# MCU2.net
KiCad netlist of a schematic drawn in Altium Designer
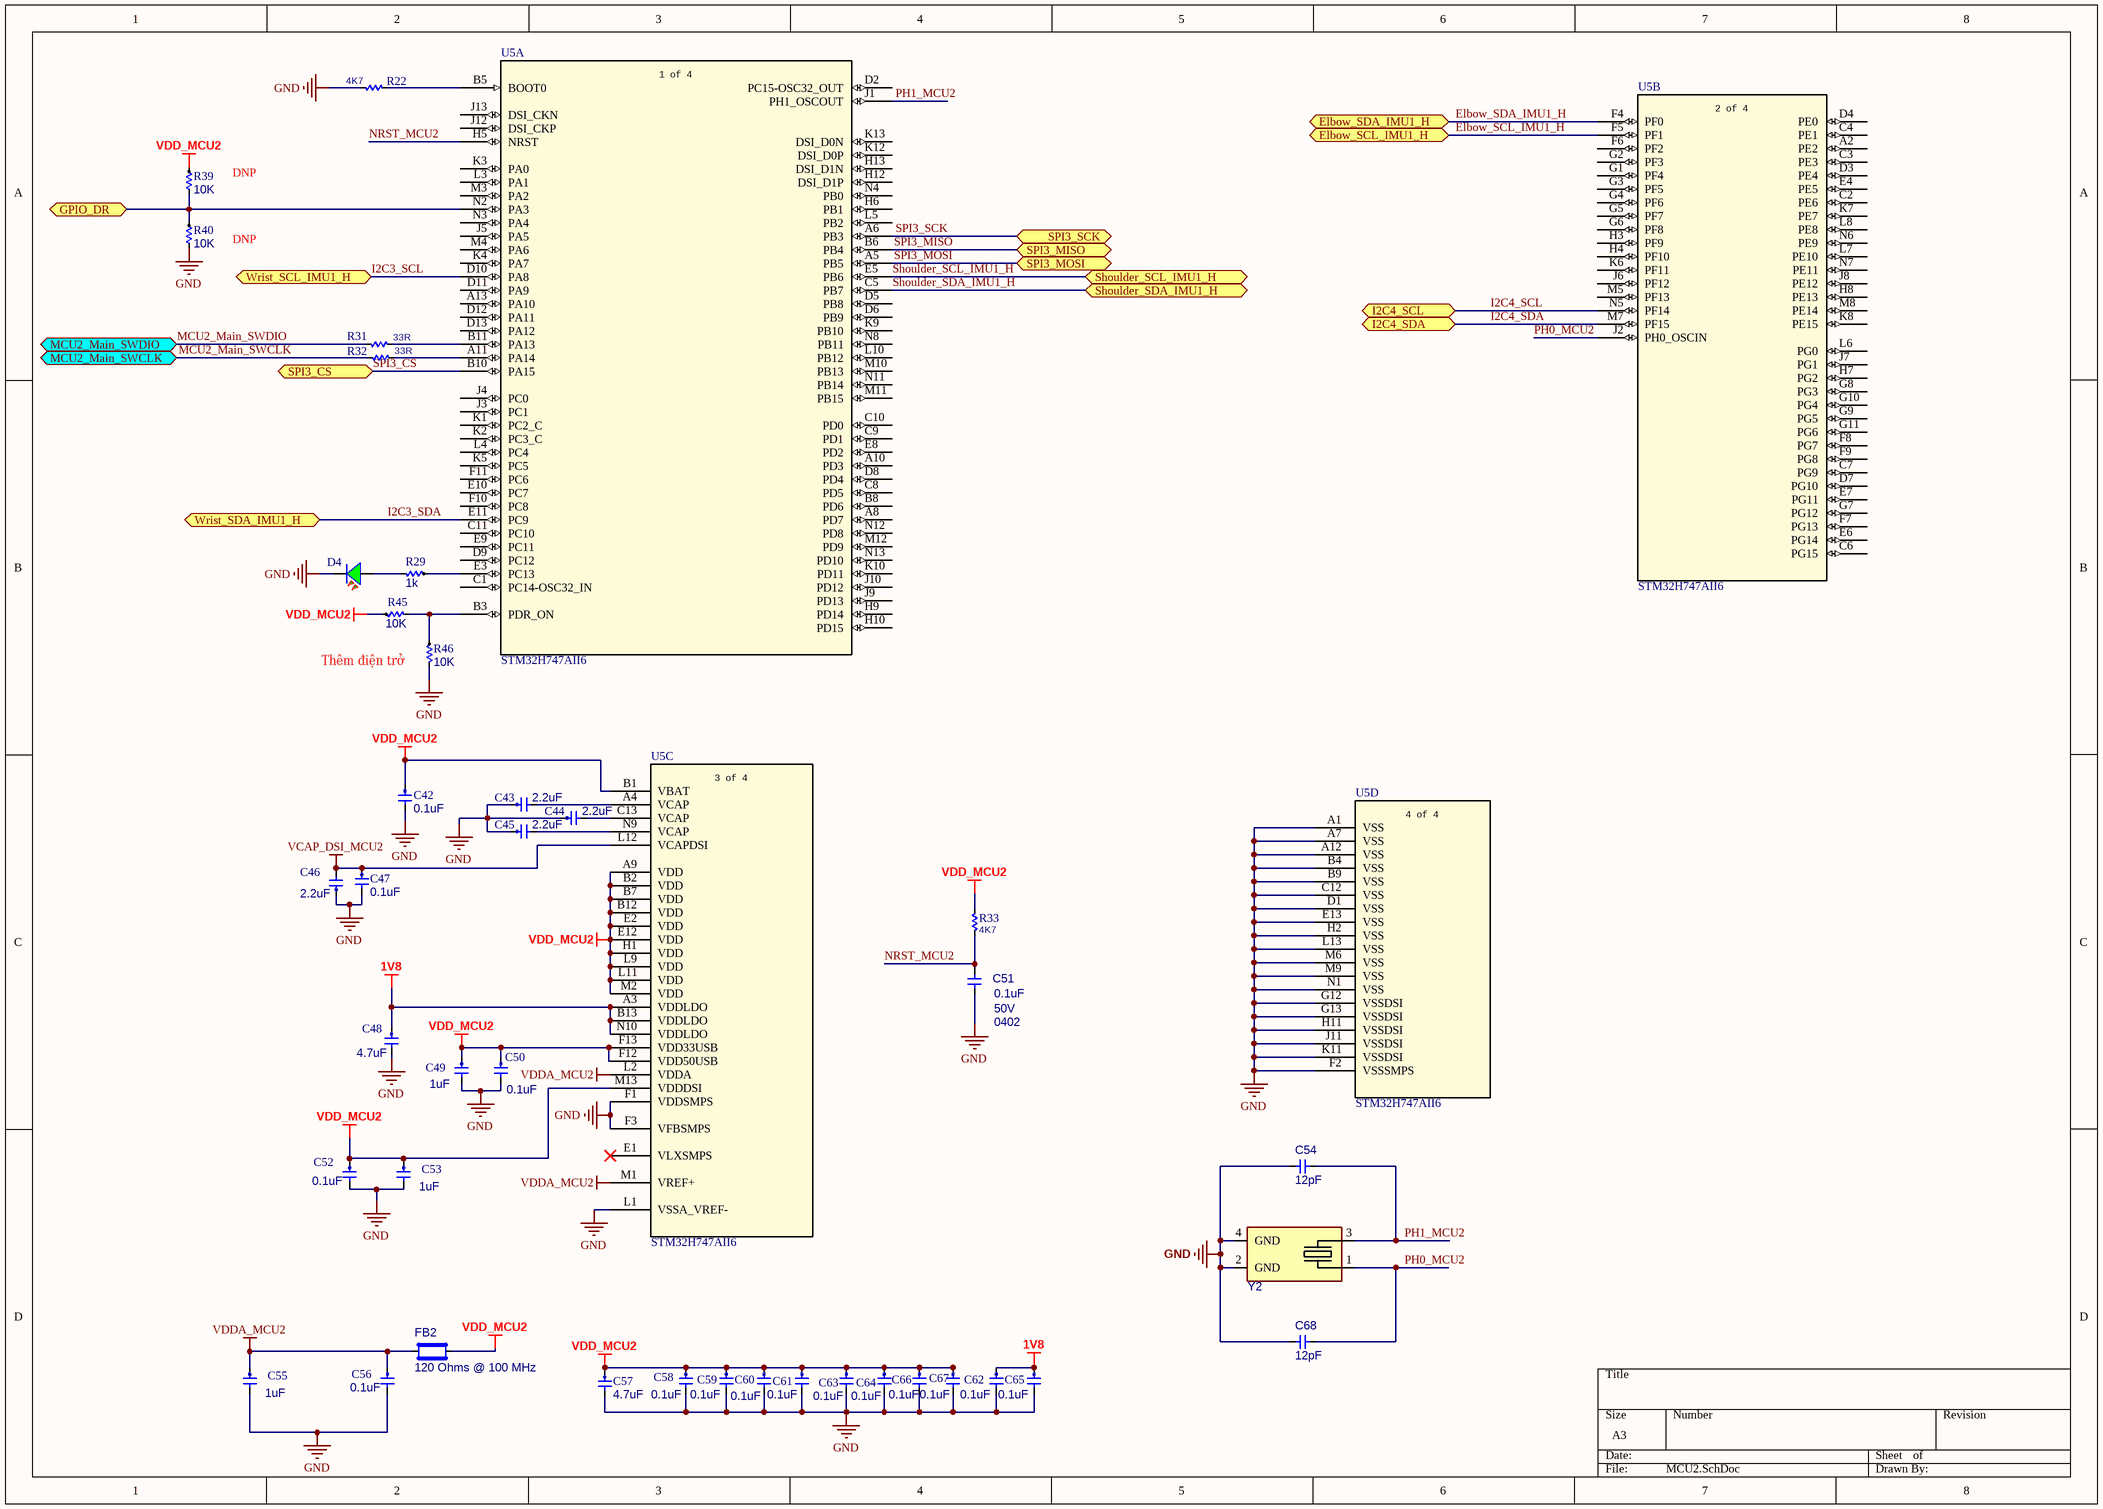
[diagram p0: MCU2.SchDoc]

(export (version "E")
  (design (tool "Eeschema 10.0.6"))
  (components
    (comp (ref "C42")
      (value "0.1uF")
      (footprint "CAP0402")
      (description "Cap 0.1uF 50V 0402")
      (fields (field (name "MP") "CC0402KRX5R9BB104") (field (name "TOLERANCE") "10%"))
      (libsource (lib "RTR (1)") (part "CAP0402 0.1uF 50V"))
    )
    (comp (ref "C43")
      (value "2.2uF")
      (footprint "CAP0402")
      (description "Cap 2.2uF 16V 0402")
      (fields (field (name "MP") "C1005X5R1C225K050BC") (field (name "VOLTAGE") "16V"))
      (libsource (lib "RTR (1)") (part "CAP0402 2.2uF 16V"))
    )
    (comp (ref "C44")
      (value "2.2uF")
      (footprint "CAP0402")
      (description "Cap 2.2uF 16V 0402")
      (fields (field (name "MP") "C1005X5R1C225K050BC") (field (name "VOLTAGE") "16V"))
      (libsource (lib "RTR (1)") (part "CAP0402 2.2uF 16V"))
    )
    (comp (ref "C45")
      (value "2.2uF")
      (footprint "CAP0402")
      (description "Cap 2.2uF 16V 0402")
      (fields (field (name "MP") "C1005X5R1C225K050BC") (field (name "VOLTAGE") "16V"))
      (libsource (lib "RTR (1)") (part "CAP0402 2.2uF 16V"))
    )
    (comp (ref "C46")
      (value "2.2uF")
      (footprint "CAP0402")
      (description "Cap 2.2uF 16V 0402")
      (fields (field (name "MP") "C1005X5R1C225K050BC") (field (name "VOLTAGE") "16V"))
      (libsource (lib "RTR (1)") (part "CAP0402 2.2uF 16V"))
    )
    (comp (ref "C47")
      (value "0.1uF")
      (footprint "CAP0402")
      (description "Cap 0.1uF 50V 0402")
      (fields (field (name "MP") "CC0402KRX5R9BB104") (field (name "TOLERANCE") "10%"))
      (libsource (lib "RTR (1)") (part "CAP0402 0.1uF 50V"))
    )
    (comp (ref "C48")
      (value "4.7uF")
      (footprint "CAP0402")
      (description "Cap 4.7uF 25V 0402")
      (fields (field (name "MP") "GRM155C61E475ME15J") (field (name "TOLERANCE") "20%"))
      (libsource (lib "RTR (1)") (part "CAP0402 4.7uF 25V"))
    )
    (comp (ref "C49")
      (value "1uF")
      (footprint "CAP0402")
      (description "Cap 1uF 50V 0402")
      (fields (field (name "MP") "GRM155R61H105KE05D") (field (name "Comment") "CAP0402 1uF 50V"))
      (libsource (lib "RTR (1)") (part "CAP0402 1uF 50V"))
    )
    (comp (ref "C50")
      (value "0.1uF")
      (footprint "CAP0402")
      (description "Cap 0.1uF 50V 0402")
      (fields (field (name "MP") "CC0402KRX5R9BB104") (field (name "TOLERANCE") "10%"))
      (libsource (lib "RTR (1)") (part "CAP0402 0.1uF 50V"))
    )
    (comp (ref "C51")
      (value "0.1uF")
      (footprint "CAP0402")
      (description "Cap 0.1uF 50V 0402")
      (fields
        (field (name "MP") "CC0402KRX5R9BB104")
        (field (name "VOLTAGE") "50V")
        (field (name "PACKAGE") "0402")
        (field (name "Comment") "CAP0402 0.1uF 50V")
      )
      (libsource (lib "RTR") (part "CAP0402 0.1uF 50V"))
    )
    (comp (ref "C52")
      (value "0.1uF")
      (footprint "CAP0402")
      (description "Cap 0.1uF 50V 0402")
      (fields (field (name "MP") "CC0402KRX5R9BB104") (field (name "TOLERANCE") "10%"))
      (libsource (lib "RTR (1)") (part "CAP0402 0.1uF 50V"))
    )
    (comp (ref "C53")
      (value "1uF")
      (footprint "CAP0402")
      (description "Cap 1uF 50V 0402")
      (fields (field (name "MP") "GRM155R61H105KE05D") (field (name "Comment") "CAP0402 1uF 50V"))
      (libsource (lib "RTR (1)") (part "CAP0402 1uF 50V"))
    )
    (comp (ref "C54")
      (value "12pF")
      (footprint "CAP0402")
      (description "Cap 12pF 50V 0402")
      (fields (field (name "Comment") "CAP0402 12pF 50V"))
      (libsource (lib "RTR") (part "CAP0402 12pF 50V"))
    )
    (comp (ref "C55")
      (value "1uF")
      (footprint "CAP0402")
      (description "Cap 1uF 50V 0402")
      (fields (field (name "MP") "GRM155R61H105KE05D") (field (name "Comment") "CAP0402 1uF 50V"))
      (libsource (lib "RTR (1)") (part "CAP0402 1uF 50V"))
    )
    (comp (ref "C56")
      (value "0.1uF")
      (footprint "CAP0402")
      (description "Cap 0.1uF 50V 0402")
      (fields (field (name "MP") "CC0402KRX5R9BB104") (field (name "TOLERANCE") "10%"))
      (libsource (lib "RTR (1)") (part "CAP0402 0.1uF 50V"))
    )
    (comp (ref "C57")
      (value "4.7uF")
      (footprint "CAP0402")
      (description "Cap 4.7uF 25V 0402")
      (fields (field (name "MP") "GRM155C61E475ME15J") (field (name "TOLERANCE") "20%"))
      (libsource (lib "RTR (1)") (part "CAP0402 4.7uF 25V"))
    )
    (comp (ref "C58")
      (value "0.1uF")
      (footprint "CAP0402")
      (description "Cap 0.1uF 50V 0402")
      (fields (field (name "MP") "CC0402KRX5R9BB104") (field (name "TOLERANCE") "10%"))
      (libsource (lib "RTR (1)") (part "CAP0402 0.1uF 50V"))
    )
    (comp (ref "C59")
      (value "0.1uF")
      (footprint "CAP0402")
      (description "Cap 0.1uF 50V 0402")
      (fields (field (name "MP") "CC0402KRX5R9BB104") (field (name "TOLERANCE") "10%"))
      (libsource (lib "RTR (1)") (part "CAP0402 0.1uF 50V"))
    )
    (comp (ref "C60")
      (value "0.1uF")
      (footprint "CAP0402")
      (description "Cap 0.1uF 50V 0402")
      (fields (field (name "MP") "CC0402KRX5R9BB104") (field (name "TOLERANCE") "10%"))
      (libsource (lib "RTR (1)") (part "CAP0402 0.1uF 50V"))
    )
    (comp (ref "C61")
      (value "0.1uF")
      (footprint "CAP0402")
      (description "Cap 0.1uF 50V 0402")
      (fields (field (name "MP") "CC0402KRX5R9BB104") (field (name "TOLERANCE") "10%"))
      (libsource (lib "RTR (1)") (part "CAP0402 0.1uF 50V"))
    )
    (comp (ref "C62")
      (value "0.1uF")
      (footprint "CAP0402")
      (description "Cap 0.1uF 50V 0402")
      (fields (field (name "MP") "CC0402KRX5R9BB104") (field (name "TOLERANCE") "10%"))
      (libsource (lib "RTR (1)") (part "CAP0402 0.1uF 50V"))
    )
    (comp (ref "C63")
      (value "0.1uF")
      (footprint "CAP0402")
      (description "Cap 0.1uF 50V 0402")
      (fields (field (name "MP") "CC0402KRX5R9BB104") (field (name "TOLERANCE") "10%"))
      (libsource (lib "RTR (1)") (part "CAP0402 0.1uF 50V"))
    )
    (comp (ref "C64")
      (value "0.1uF")
      (footprint "CAP0402")
      (description "Cap 0.1uF 50V 0402")
      (fields (field (name "MP") "CC0402KRX5R9BB104") (field (name "TOLERANCE") "10%"))
      (libsource (lib "RTR (1)") (part "CAP0402 0.1uF 50V"))
    )
    (comp (ref "C65")
      (value "0.1uF")
      (footprint "CAP0402")
      (description "Cap 0.1uF 50V 0402")
      (fields (field (name "MP") "CC0402KRX5R9BB104") (field (name "TOLERANCE") "10%"))
      (libsource (lib "RTR (1)") (part "CAP0402 0.1uF 50V"))
    )
    (comp (ref "C66")
      (value "0.1uF")
      (footprint "CAP0402")
      (description "Cap 0.1uF 50V 0402")
      (fields (field (name "MP") "CC0402KRX5R9BB104") (field (name "TOLERANCE") "10%"))
      (libsource (lib "RTR (1)") (part "CAP0402 0.1uF 50V"))
    )
    (comp (ref "C67")
      (value "0.1uF")
      (footprint "CAP0402")
      (description "Cap 0.1uF 50V 0402")
      (fields (field (name "MP") "CC0402KRX5R9BB104") (field (name "TOLERANCE") "10%"))
      (libsource (lib "RTR (1)") (part "CAP0402 0.1uF 50V"))
    )
    (comp (ref "C68")
      (value "12pF")
      (footprint "CAP0402")
      (description "Cap 12pF 50V 0402")
      (fields (field (name "Comment") "CAP0402 12pF 50V"))
      (libsource (lib "RTR") (part "CAP0402 12pF 50V"))
    )
    (comp (ref "D4")
      (value "SML-310MTT86")
      (footprint "LED0603 GREEN")
      (description "LED GREEN CLEAR 0603 SMD")
      (libsource (lib "HeraJetson_Modified") (part "CMP-01130-2"))
    )
    (comp (ref "FB2")
      (value "BLM15PX121SZ1D")
      (footprint "FERRIT0402")
      (description "120 Ohms @ 100 MHz 1 Power Line Ferrite Bead 0402 (1005 Metric) 2A 55mOhm")
      (fields (field (name "IMPEDANCE @ FREQUENCY") "120 Ohms @ 100 MHz"))
      (libsource (lib "RTR") (part "BLM15PX121SZ1D"))
    )
    (comp (ref "R22")
      (value "4K7")
      (footprint "RES0402")
      (description "RES 4K7 0402")
      (fields (field (name "MP") "RC0402JR-074K7L") (field (name "Comment") "RES0402 4K7"))
      (libsource (lib "RTR") (part "RES0402 4K7"))
    )
    (comp (ref "R29")
      (value "1k")
      (footprint "RES0402")
      (description "RES 1K 0402")
      (fields (field (name "MP") "RC0402FR-071KL") (field (name "TOLERANCE") "1%"))
      (libsource (lib "RTR (1)") (part "RES0402 1K"))
    )
    (comp (ref "R31")
      (value "33R")
      (footprint "RES0402")
      (description "RES 33R 0402")
      (fields (field (name "MP") "RC0402FR-0733RL") (field (name "Comment") "RES0402 33R"))
      (libsource (lib "RTR (1)") (part "RES0402 33R"))
    )
    (comp (ref "R32")
      (value "33R")
      (footprint "RES0402")
      (description "RES 33R 0402")
      (fields (field (name "MP") "RC0402FR-0733RL") (field (name "Comment") "RES0402 33R"))
      (libsource (lib "RTR (1)") (part "RES0402 33R"))
    )
    (comp (ref "R33")
      (value "4K7")
      (footprint "RES0402")
      (description "RES 4K7 0402")
      (fields (field (name "MP") "RC0402JR-074K7L") (field (name "Comment") "RES0402 4K7"))
      (libsource (lib "RTR") (part "RES0402 4K7"))
    )
    (comp (ref "R39")
      (value "10K")
      (footprint "RES0402")
      (description "RES 10K 0402")
      (fields (field (name "MP") "RC0402FR-0710KL") (field (name "TOLERANCE") "1%"))
      (libsource (lib "RTR (1)") (part "RES0402 10K"))
    )
    (comp (ref "R40")
      (value "10K")
      (footprint "RES0402")
      (description "RES 10K 0402")
      (fields (field (name "MP") "RC0402FR-0710KL") (field (name "TOLERANCE") "1%"))
      (libsource (lib "RTR (1)") (part "RES0402 10K"))
    )
    (comp (ref "R45")
      (value "10K")
      (footprint "RES0402")
      (description "RES 10K 0402")
      (fields (field (name "MP") "RC0402FR-0710KL") (field (name "TOLERANCE") "1%"))
      (libsource (lib "RTR (1)") (part "RES0402 10K"))
    )
    (comp (ref "R46")
      (value "10K")
      (footprint "RES0402")
      (description "RES 10K 0402")
      (fields (field (name "MP") "RC0402FR-0710KL") (field (name "TOLERANCE") "1%"))
      (libsource (lib "RTR (1)") (part "RES0402 10K"))
    )
    (comp (ref "U5")
      (value "STM32H747AII6")
      (footprint "UFBGA169")
      (fields (field (name "COPYRIGHT") "Copyright (C) 2026 Ultra Librarian. All rights reserved."))
      (libsource (lib "RTR") (part "STM32H747AII6"))
    )
    (comp (ref "Y2")
      (value "ECS-240-12-37B-CKY-TR")
      (footprint "XTAL_ECS-240-12-37B-CKY-TR")
      (description "Crystal 24 MHz ±10ppm 12pF 50 Ohms 4-SMD, No Lead")
      (libsource (lib "RTR") (part "ECS-240-12-37B-CKY-TR"))
    )
  )
  (nets
    (net (code "1") (name "/Elbow_SCL_IMU1_H") (class "Default")
      (node (ref "U5") (pin "F5") (pinfunction "PF1_F5") (pintype "bidirectional"))
    )
    (net (code "2") (name "/Elbow_SDA_IMU1_H") (class "Default")
      (node (ref "U5") (pin "F4") (pinfunction "PF0_F4") (pintype "bidirectional"))
    )
    (net (code "3") (name "/GPIO_DR") (class "Default")
      (node (ref "R39") (pin "1") (pinfunction "1_1") (pintype "passive"))
      (node (ref "R40") (pin "2") (pinfunction "2_2") (pintype "passive"))
      (node (ref "U5") (pin "N2") (pinfunction "PA3_N2") (pintype "bidirectional"))
    )
    (net (code "4") (name "/I2C3_SCL") (class "Default")
      (node (ref "U5") (pin "D10") (pinfunction "PA8_D10") (pintype "bidirectional"))
    )
    (net (code "5") (name "/I2C3_SDA") (class "Default")
      (node (ref "U5") (pin "E11") (pinfunction "PC9_E11") (pintype "bidirectional"))
    )
    (net (code "6") (name "/I2C4_SCL") (class "Default")
      (node (ref "U5") (pin "N5") (pinfunction "PF14_N5") (pintype "bidirectional"))
    )
    (net (code "7") (name "/I2C4_SDA") (class "Default")
      (node (ref "U5") (pin "M7") (pinfunction "PF15_M7") (pintype "bidirectional"))
    )
    (net (code "8") (name "/MCU2_Main_SWCLK") (class "Default")
      (node (ref "R32") (pin "1") (pinfunction "1_1") (pintype "passive"))
    )
    (net (code "9") (name "/MCU2_Main_SWDIO") (class "Default")
      (node (ref "R31") (pin "1") (pinfunction "1_1") (pintype "passive"))
    )
    (net (code "10") (name "/NRST_MCU2") (class "Default")
      (node (ref "C51") (pin "2") (pinfunction "2_2") (pintype "passive"))
      (node (ref "R33") (pin "1") (pinfunction "1_1") (pintype "passive"))
      (node (ref "U5") (pin "H5") (pinfunction "NRST_H5") (pintype "bidirectional"))
    )
    (net (code "11") (name "/PH0_MCU2") (class "Default")
      (node (ref "C68") (pin "1") (pinfunction "1_1") (pintype "passive"))
      (node (ref "U5") (pin "J2") (pinfunction "PH0_OSCIN_J2") (pintype "bidirectional"))
      (node (ref "Y2") (pin "1") (pinfunction "IO_1") (pintype "passive"))
    )
    (net (code "12") (name "/PH1_MCU2") (class "Default")
      (node (ref "C54") (pin "1") (pinfunction "1_1") (pintype "passive"))
      (node (ref "U5") (pin "J1") (pinfunction "PH1_OSCOUT_J1") (pintype "bidirectional"))
      (node (ref "Y2") (pin "3") (pinfunction "IO_3") (pintype "passive"))
    )
    (net (code "13") (name "/SPI3_CS") (class "Default")
      (node (ref "U5") (pin "B10") (pinfunction "PA15_B10") (pintype "bidirectional"))
    )
    (net (code "14") (name "/SPI3_MISO") (class "Default")
      (node (ref "U5") (pin "B6") (pinfunction "PB4_B6") (pintype "bidirectional"))
    )
    (net (code "15") (name "/SPI3_MOSI") (class "Default")
      (node (ref "U5") (pin "A5") (pinfunction "PB5_A5") (pintype "bidirectional"))
    )
    (net (code "16") (name "/SPI3_SCK") (class "Default")
      (node (ref "U5") (pin "A6") (pinfunction "PB3_A6") (pintype "bidirectional"))
    )
    (net (code "17") (name "/Shoulder_SCL_IMU1_H") (class "Default")
      (node (ref "U5") (pin "E5") (pinfunction "PB6_E5") (pintype "bidirectional"))
    )
    (net (code "18") (name "/Shoulder_SDA_IMU1_H") (class "Default")
      (node (ref "U5") (pin "C5") (pinfunction "PB7_C5") (pintype "bidirectional"))
    )
    (net (code "19") (name "1V8") (class "Default")
      (node (ref "C48") (pin "1") (pinfunction "1_1") (pintype "passive"))
      (node (ref "C62") (pin "1") (pinfunction "1_1") (pintype "passive"))
      (node (ref "C65") (pin "1") (pinfunction "1_1") (pintype "passive"))
      (node (ref "U5") (pin "A3") (pinfunction "VDDLDO_A3") (pintype "power_in"))
      (node (ref "U5") (pin "B13") (pinfunction "VDDLDO_B13") (pintype "power_in"))
      (node (ref "U5") (pin "N10") (pinfunction "VDDLDO_N10") (pintype "power_in"))
    )
    (net (code "20") (name "GND") (class "Default")
      (node (ref "C42") (pin "2") (pinfunction "2_2") (pintype "passive"))
      (node (ref "C43") (pin "1") (pinfunction "1_1") (pintype "passive"))
      (node (ref "C44") (pin "1") (pinfunction "1_1") (pintype "passive"))
      (node (ref "C45") (pin "1") (pinfunction "1_1") (pintype "passive"))
      (node (ref "C46") (pin "1") (pinfunction "1_1") (pintype "passive"))
      (node (ref "C47") (pin "2") (pinfunction "2_2") (pintype "passive"))
      (node (ref "C48") (pin "2") (pinfunction "2_2") (pintype "passive"))
      (node (ref "C49") (pin "2") (pinfunction "2_2") (pintype "passive"))
      (node (ref "C50") (pin "2") (pinfunction "2_2") (pintype "passive"))
      (node (ref "C51") (pin "1") (pinfunction "1_1") (pintype "passive"))
      (node (ref "C52") (pin "2") (pinfunction "2_2") (pintype "passive"))
      (node (ref "C53") (pin "2") (pinfunction "2_2") (pintype "passive"))
      (node (ref "C54") (pin "2") (pinfunction "2_2") (pintype "passive"))
      (node (ref "C55") (pin "2") (pinfunction "2_2") (pintype "passive"))
      (node (ref "C56") (pin "2") (pinfunction "2_2") (pintype "passive"))
      (node (ref "C57") (pin "2") (pinfunction "2_2") (pintype "passive"))
      (node (ref "C58") (pin "2") (pinfunction "2_2") (pintype "passive"))
      (node (ref "C59") (pin "2") (pinfunction "2_2") (pintype "passive"))
      (node (ref "C60") (pin "2") (pinfunction "2_2") (pintype "passive"))
      (node (ref "C61") (pin "2") (pinfunction "2_2") (pintype "passive"))
      (node (ref "C62") (pin "2") (pinfunction "2_2") (pintype "passive"))
      (node (ref "C63") (pin "2") (pinfunction "2_2") (pintype "passive"))
      (node (ref "C64") (pin "2") (pinfunction "2_2") (pintype "passive"))
      (node (ref "C65") (pin "2") (pinfunction "2_2") (pintype "passive"))
      (node (ref "C66") (pin "2") (pinfunction "2_2") (pintype "passive"))
      (node (ref "C67") (pin "2") (pinfunction "2_2") (pintype "passive"))
      (node (ref "C68") (pin "2") (pinfunction "2_2") (pintype "passive"))
      (node (ref "D4") (pin "1") (pinfunction "1_1") (pintype "passive"))
      (node (ref "R22") (pin "1") (pinfunction "1_1") (pintype "passive"))
      (node (ref "R40") (pin "1") (pinfunction "1_1") (pintype "passive"))
      (node (ref "R46") (pin "1") (pinfunction "1_1") (pintype "passive"))
      (node (ref "U5") (pin "A1") (pinfunction "VSS_A1") (pintype "power_in"))
      (node (ref "U5") (pin "A12") (pinfunction "VSS_A12") (pintype "power_in"))
      (node (ref "U5") (pin "A7") (pinfunction "VSS_A7") (pintype "power_in"))
      (node (ref "U5") (pin "B4") (pinfunction "VSS_B4") (pintype "power_in"))
      (node (ref "U5") (pin "B9") (pinfunction "VSS_B9") (pintype "power_in"))
      (node (ref "U5") (pin "C12") (pinfunction "VSS_C12") (pintype "power_in"))
      (node (ref "U5") (pin "D1") (pinfunction "VSS_D1") (pintype "power_in"))
      (node (ref "U5") (pin "E13") (pinfunction "VSS_E13") (pintype "power_in"))
      (node (ref "U5") (pin "F1") (pinfunction "VDDSMPS_F1") (pintype "power_in"))
      (node (ref "U5") (pin "F2") (pinfunction "VSSSMPS_F2") (pintype "power_in"))
      (node (ref "U5") (pin "F3") (pinfunction "VFBSMPS_F3") (pintype "power_in"))
      (node (ref "U5") (pin "G12") (pinfunction "VSSDSI_G12") (pintype "power_in"))
      (node (ref "U5") (pin "G13") (pinfunction "VSSDSI_G13") (pintype "power_in"))
      (node (ref "U5") (pin "H11") (pinfunction "VSSDSI_H11") (pintype "power_in"))
      (node (ref "U5") (pin "H2") (pinfunction "VSS_H2") (pintype "power_in"))
      (node (ref "U5") (pin "J11") (pinfunction "VSSDSI_J11") (pintype "power_in"))
      (node (ref "U5") (pin "K11") (pinfunction "VSSDSI_K11") (pintype "power_in"))
      (node (ref "U5") (pin "L1") (pinfunction "VSSA_VREF-_L1") (pintype "power_in"))
      (node (ref "U5") (pin "L13") (pinfunction "VSS_L13") (pintype "power_in"))
      (node (ref "U5") (pin "M6") (pinfunction "VSS_M6") (pintype "power_in"))
      (node (ref "U5") (pin "M9") (pinfunction "VSS_M9") (pintype "power_in"))
      (node (ref "U5") (pin "N1") (pinfunction "VSS_N1") (pintype "power_in"))
      (node (ref "Y2") (pin "2") (pinfunction "GND_2") (pintype "passive"))
      (node (ref "Y2") (pin "4") (pinfunction "GND_4") (pintype "passive"))
    )
    (net (code "21") (name "Net-(C43-Pad2)") (class "Default")
      (node (ref "C43") (pin "2") (pinfunction "2_2") (pintype "passive"))
      (node (ref "U5") (pin "A4") (pinfunction "VCAP_A4") (pintype "power_in"))
    )
    (net (code "22") (name "Net-(C44-Pad2)") (class "Default")
      (node (ref "C44") (pin "2") (pinfunction "2_2") (pintype "passive"))
      (node (ref "U5") (pin "C13") (pinfunction "VCAP_C13") (pintype "power_in"))
    )
    (net (code "23") (name "Net-(C45-Pad2)") (class "Default")
      (node (ref "C45") (pin "2") (pinfunction "2_2") (pintype "passive"))
      (node (ref "U5") (pin "N9") (pinfunction "VCAP_N9") (pintype "power_in"))
    )
    (net (code "24") (name "Net-(D4-Pad2)") (class "Default")
      (node (ref "D4") (pin "2") (pinfunction "2_2") (pintype "passive"))
      (node (ref "R29") (pin "1") (pinfunction "1_1") (pintype "passive"))
    )
    (net (code "25") (name "Net-(U5A-BOOT0)") (class "Default")
      (node (ref "R22") (pin "2") (pinfunction "2_2") (pintype "passive"))
      (node (ref "U5") (pin "B5") (pinfunction "BOOT0_B5") (pintype "input"))
    )
    (net (code "26") (name "Net-(U5A-PA13)") (class "Default")
      (node (ref "R31") (pin "2") (pinfunction "2_2") (pintype "passive"))
      (node (ref "U5") (pin "B11") (pinfunction "PA13_B11") (pintype "bidirectional"))
    )
    (net (code "27") (name "Net-(U5A-PA14)") (class "Default")
      (node (ref "R32") (pin "2") (pinfunction "2_2") (pintype "passive"))
      (node (ref "U5") (pin "A11") (pinfunction "PA14_A11") (pintype "bidirectional"))
    )
    (net (code "28") (name "Net-(U5A-PC13)") (class "Default")
      (node (ref "R29") (pin "2") (pinfunction "2_2") (pintype "passive"))
      (node (ref "U5") (pin "E3") (pinfunction "PC13_E3") (pintype "bidirectional"))
    )
    (net (code "29") (name "Net-(U5A-PDR_ON)") (class "Default")
      (node (ref "R45") (pin "1") (pinfunction "1_1") (pintype "passive"))
      (node (ref "R46") (pin "2") (pinfunction "2_2") (pintype "passive"))
      (node (ref "U5") (pin "B3") (pinfunction "PDR_ON_B3") (pintype "bidirectional"))
    )
    (net (code "30") (name "VCAP_DSI_MCU2") (class "Default")
      (node (ref "C46") (pin "2") (pinfunction "2_2") (pintype "passive"))
      (node (ref "C47") (pin "1") (pinfunction "1_1") (pintype "passive"))
      (node (ref "U5") (pin "L12") (pinfunction "VCAPDSI_L12") (pintype "power_in"))
    )
    (net (code "31") (name "VDDA_MCU2") (class "Default")
      (node (ref "C55") (pin "1") (pinfunction "1_1") (pintype "passive"))
      (node (ref "C56") (pin "1") (pinfunction "1_1") (pintype "passive"))
      (node (ref "FB2") (pin "1") (pinfunction "1_1") (pintype "passive"))
      (node (ref "U5") (pin "L2") (pinfunction "VDDA_L2") (pintype "power_in"))
      (node (ref "U5") (pin "M1") (pinfunction "VREF+_M1") (pintype "power_in"))
    )
    (net (code "32") (name "VDD_MCU2") (class "Default")
      (node (ref "C42") (pin "1") (pinfunction "1_1") (pintype "passive"))
      (node (ref "C49") (pin "1") (pinfunction "1_1") (pintype "passive"))
      (node (ref "C50") (pin "1") (pinfunction "1_1") (pintype "passive"))
      (node (ref "C52") (pin "1") (pinfunction "1_1") (pintype "passive"))
      (node (ref "C53") (pin "1") (pinfunction "1_1") (pintype "passive"))
      (node (ref "C57") (pin "1") (pinfunction "1_1") (pintype "passive"))
      (node (ref "C58") (pin "1") (pinfunction "1_1") (pintype "passive"))
      (node (ref "C59") (pin "1") (pinfunction "1_1") (pintype "passive"))
      (node (ref "C60") (pin "1") (pinfunction "1_1") (pintype "passive"))
      (node (ref "C61") (pin "1") (pinfunction "1_1") (pintype "passive"))
      (node (ref "C63") (pin "1") (pinfunction "1_1") (pintype "passive"))
      (node (ref "C64") (pin "1") (pinfunction "1_1") (pintype "passive"))
      (node (ref "C66") (pin "1") (pinfunction "1_1") (pintype "passive"))
      (node (ref "C67") (pin "1") (pinfunction "1_1") (pintype "passive"))
      (node (ref "FB2") (pin "2") (pinfunction "2_2") (pintype "passive"))
      (node (ref "R33") (pin "2") (pinfunction "2_2") (pintype "passive"))
      (node (ref "R39") (pin "2") (pinfunction "2_2") (pintype "passive"))
      (node (ref "R45") (pin "2") (pinfunction "2_2") (pintype "passive"))
      (node (ref "U5") (pin "A9") (pinfunction "VDD_A9") (pintype "power_in"))
      (node (ref "U5") (pin "B1") (pinfunction "VBAT_B1") (pintype "power_in"))
      (node (ref "U5") (pin "B12") (pinfunction "VDD_B12") (pintype "power_in"))
      (node (ref "U5") (pin "B2") (pinfunction "VDD_B2") (pintype "power_in"))
      (node (ref "U5") (pin "B7") (pinfunction "VDD_B7") (pintype "power_in"))
      (node (ref "U5") (pin "E12") (pinfunction "VDD_E12") (pintype "power_in"))
      (node (ref "U5") (pin "E2") (pinfunction "VDD_E2") (pintype "power_in"))
      (node (ref "U5") (pin "F12") (pinfunction "VDD50USB_F12") (pintype "power_in"))
      (node (ref "U5") (pin "F13") (pinfunction "VDD33USB_F13") (pintype "power_in"))
      (node (ref "U5") (pin "H1") (pinfunction "VDD_H1") (pintype "power_in"))
      (node (ref "U5") (pin "L11") (pinfunction "VDD_L11") (pintype "power_in"))
      (node (ref "U5") (pin "L9") (pinfunction "VDD_L9") (pintype "power_in"))
      (node (ref "U5") (pin "M13") (pinfunction "VDDDSI_M13") (pintype "power_in"))
      (node (ref "U5") (pin "M2") (pinfunction "VDD_M2") (pintype "power_in"))
    )
    (net (code "33") (name "unconnected-(U5A-DSI_CKN-PadJ13)") (class "Default")
      (node (ref "U5") (pin "J13") (pinfunction "DSI_CKN_J13") (pintype "bidirectional"))
    )
    (net (code "34") (name "unconnected-(U5A-DSI_CKP-PadJ12)") (class "Default")
      (node (ref "U5") (pin "J12") (pinfunction "DSI_CKP_J12") (pintype "bidirectional"))
    )
    (net (code "35") (name "unconnected-(U5A-DSI_D0N-PadK13)") (class "Default")
      (node (ref "U5") (pin "K13") (pinfunction "DSI_D0N_K13") (pintype "bidirectional"))
    )
    (net (code "36") (name "unconnected-(U5A-DSI_D0P-PadK12)") (class "Default")
      (node (ref "U5") (pin "K12") (pinfunction "DSI_D0P_K12") (pintype "bidirectional"))
    )
    (net (code "37") (name "unconnected-(U5A-DSI_D1N-PadH13)") (class "Default")
      (node (ref "U5") (pin "H13") (pinfunction "DSI_D1N_H13") (pintype "bidirectional"))
    )
    (net (code "38") (name "unconnected-(U5A-DSI_D1P-PadH12)") (class "Default")
      (node (ref "U5") (pin "H12") (pinfunction "DSI_D1P_H12") (pintype "bidirectional"))
    )
    (net (code "39") (name "unconnected-(U5A-PA0-PadK3)") (class "Default")
      (node (ref "U5") (pin "K3") (pinfunction "PA0_K3") (pintype "bidirectional"))
    )
    (net (code "40") (name "unconnected-(U5A-PA1-PadL3)") (class "Default")
      (node (ref "U5") (pin "L3") (pinfunction "PA1_L3") (pintype "bidirectional"))
    )
    (net (code "41") (name "unconnected-(U5A-PA2-PadM3)") (class "Default")
      (node (ref "U5") (pin "M3") (pinfunction "PA2_M3") (pintype "bidirectional"))
    )
    (net (code "42") (name "unconnected-(U5A-PA4-PadN3)") (class "Default")
      (node (ref "U5") (pin "N3") (pinfunction "PA4_N3") (pintype "bidirectional"))
    )
    (net (code "43") (name "unconnected-(U5A-PA5-PadJ5)") (class "Default")
      (node (ref "U5") (pin "J5") (pinfunction "PA5_J5") (pintype "bidirectional"))
    )
    (net (code "44") (name "unconnected-(U5A-PA6-PadM4)") (class "Default")
      (node (ref "U5") (pin "M4") (pinfunction "PA6_M4") (pintype "bidirectional"))
    )
    (net (code "45") (name "unconnected-(U5A-PA7-PadK4)") (class "Default")
      (node (ref "U5") (pin "K4") (pinfunction "PA7_K4") (pintype "bidirectional"))
    )
    (net (code "46") (name "unconnected-(U5A-PA9-PadD11)") (class "Default")
      (node (ref "U5") (pin "D11") (pinfunction "PA9_D11") (pintype "bidirectional"))
    )
    (net (code "47") (name "unconnected-(U5A-PA10-PadA13)") (class "Default")
      (node (ref "U5") (pin "A13") (pinfunction "PA10_A13") (pintype "bidirectional"))
    )
    (net (code "48") (name "unconnected-(U5A-PA11-PadD12)") (class "Default")
      (node (ref "U5") (pin "D12") (pinfunction "PA11_D12") (pintype "bidirectional"))
    )
    (net (code "49") (name "unconnected-(U5A-PA12-PadD13)") (class "Default")
      (node (ref "U5") (pin "D13") (pinfunction "PA12_D13") (pintype "bidirectional"))
    )
    (net (code "50") (name "unconnected-(U5A-PB0-PadN4)") (class "Default")
      (node (ref "U5") (pin "N4") (pinfunction "PB0_N4") (pintype "bidirectional"))
    )
    (net (code "51") (name "unconnected-(U5A-PB1-PadH6)") (class "Default")
      (node (ref "U5") (pin "H6") (pinfunction "PB1_H6") (pintype "bidirectional"))
    )
    (net (code "52") (name "unconnected-(U5A-PB2-PadL5)") (class "Default")
      (node (ref "U5") (pin "L5") (pinfunction "PB2_L5") (pintype "bidirectional"))
    )
    (net (code "53") (name "unconnected-(U5A-PB8-PadD5)") (class "Default")
      (node (ref "U5") (pin "D5") (pinfunction "PB8_D5") (pintype "bidirectional"))
    )
    (net (code "54") (name "unconnected-(U5A-PB9-PadD6)") (class "Default")
      (node (ref "U5") (pin "D6") (pinfunction "PB9_D6") (pintype "bidirectional"))
    )
    (net (code "55") (name "unconnected-(U5A-PB10-PadK9)") (class "Default")
      (node (ref "U5") (pin "K9") (pinfunction "PB10_K9") (pintype "bidirectional"))
    )
    (net (code "56") (name "unconnected-(U5A-PB11-PadN8)") (class "Default")
      (node (ref "U5") (pin "N8") (pinfunction "PB11_N8") (pintype "bidirectional"))
    )
    (net (code "57") (name "unconnected-(U5A-PB12-PadL10)") (class "Default")
      (node (ref "U5") (pin "L10") (pinfunction "PB12_L10") (pintype "bidirectional"))
    )
    (net (code "58") (name "unconnected-(U5A-PB13-PadM10)") (class "Default")
      (node (ref "U5") (pin "M10") (pinfunction "PB13_M10") (pintype "bidirectional"))
    )
    (net (code "59") (name "unconnected-(U5A-PB14-PadN11)") (class "Default")
      (node (ref "U5") (pin "N11") (pinfunction "PB14_N11") (pintype "bidirectional"))
    )
    (net (code "60") (name "unconnected-(U5A-PB15-PadM11)") (class "Default")
      (node (ref "U5") (pin "M11") (pinfunction "PB15_M11") (pintype "bidirectional"))
    )
    (net (code "61") (name "unconnected-(U5A-PC0-PadJ4)") (class "Default")
      (node (ref "U5") (pin "J4") (pinfunction "PC0_J4") (pintype "bidirectional"))
    )
    (net (code "62") (name "unconnected-(U5A-PC1-PadJ3)") (class "Default")
      (node (ref "U5") (pin "J3") (pinfunction "PC1_J3") (pintype "bidirectional"))
    )
    (net (code "63") (name "unconnected-(U5A-PC2_C-PadK1)") (class "Default")
      (node (ref "U5") (pin "K1") (pinfunction "PC2_C_K1") (pintype "bidirectional"))
    )
    (net (code "64") (name "unconnected-(U5A-PC3_C-PadK2)") (class "Default")
      (node (ref "U5") (pin "K2") (pinfunction "PC3_C_K2") (pintype "bidirectional"))
    )
    (net (code "65") (name "unconnected-(U5A-PC4-PadL4)") (class "Default")
      (node (ref "U5") (pin "L4") (pinfunction "PC4_L4") (pintype "bidirectional"))
    )
    (net (code "66") (name "unconnected-(U5A-PC5-PadK5)") (class "Default")
      (node (ref "U5") (pin "K5") (pinfunction "PC5_K5") (pintype "bidirectional"))
    )
    (net (code "67") (name "unconnected-(U5A-PC6-PadF11)") (class "Default")
      (node (ref "U5") (pin "F11") (pinfunction "PC6_F11") (pintype "bidirectional"))
    )
    (net (code "68") (name "unconnected-(U5A-PC7-PadE10)") (class "Default")
      (node (ref "U5") (pin "E10") (pinfunction "PC7_E10") (pintype "bidirectional"))
    )
    (net (code "69") (name "unconnected-(U5A-PC8-PadF10)") (class "Default")
      (node (ref "U5") (pin "F10") (pinfunction "PC8_F10") (pintype "bidirectional"))
    )
    (net (code "70") (name "unconnected-(U5A-PC10-PadC11)") (class "Default")
      (node (ref "U5") (pin "C11") (pinfunction "PC10_C11") (pintype "bidirectional"))
    )
    (net (code "71") (name "unconnected-(U5A-PC11-PadE9)") (class "Default")
      (node (ref "U5") (pin "E9") (pinfunction "PC11_E9") (pintype "bidirectional"))
    )
    (net (code "72") (name "unconnected-(U5A-PC12-PadD9)") (class "Default")
      (node (ref "U5") (pin "D9") (pinfunction "PC12_D9") (pintype "bidirectional"))
    )
    (net (code "73") (name "unconnected-(U5A-PC14-OSC32_IN-PadC1)") (class "Default")
      (node (ref "U5") (pin "C1") (pinfunction "PC14-OSC32_IN_C1") (pintype "bidirectional"))
    )
    (net (code "74") (name "unconnected-(U5A-PC15-OSC32_OUT-PadD2)") (class "Default")
      (node (ref "U5") (pin "D2") (pinfunction "PC15-OSC32_OUT_D2") (pintype "bidirectional"))
    )
    (net (code "75") (name "unconnected-(U5A-PD0-PadC10)") (class "Default")
      (node (ref "U5") (pin "C10") (pinfunction "PD0_C10") (pintype "bidirectional"))
    )
    (net (code "76") (name "unconnected-(U5A-PD1-PadC9)") (class "Default")
      (node (ref "U5") (pin "C9") (pinfunction "PD1_C9") (pintype "bidirectional"))
    )
    (net (code "77") (name "unconnected-(U5A-PD2-PadE8)") (class "Default")
      (node (ref "U5") (pin "E8") (pinfunction "PD2_E8") (pintype "bidirectional"))
    )
    (net (code "78") (name "unconnected-(U5A-PD3-PadA10)") (class "Default")
      (node (ref "U5") (pin "A10") (pinfunction "PD3_A10") (pintype "bidirectional"))
    )
    (net (code "79") (name "unconnected-(U5A-PD4-PadD8)") (class "Default")
      (node (ref "U5") (pin "D8") (pinfunction "PD4_D8") (pintype "bidirectional"))
    )
    (net (code "80") (name "unconnected-(U5A-PD5-PadC8)") (class "Default")
      (node (ref "U5") (pin "C8") (pinfunction "PD5_C8") (pintype "bidirectional"))
    )
    (net (code "81") (name "unconnected-(U5A-PD6-PadB8)") (class "Default")
      (node (ref "U5") (pin "B8") (pinfunction "PD6_B8") (pintype "bidirectional"))
    )
    (net (code "82") (name "unconnected-(U5A-PD7-PadA8)") (class "Default")
      (node (ref "U5") (pin "A8") (pinfunction "PD7_A8") (pintype "bidirectional"))
    )
    (net (code "83") (name "unconnected-(U5A-PD8-PadN12)") (class "Default")
      (node (ref "U5") (pin "N12") (pinfunction "PD8_N12") (pintype "bidirectional"))
    )
    (net (code "84") (name "unconnected-(U5A-PD9-PadM12)") (class "Default")
      (node (ref "U5") (pin "M12") (pinfunction "PD9_M12") (pintype "bidirectional"))
    )
    (net (code "85") (name "unconnected-(U5A-PD10-PadN13)") (class "Default")
      (node (ref "U5") (pin "N13") (pinfunction "PD10_N13") (pintype "bidirectional"))
    )
    (net (code "86") (name "unconnected-(U5A-PD11-PadK10)") (class "Default")
      (node (ref "U5") (pin "K10") (pinfunction "PD11_K10") (pintype "bidirectional"))
    )
    (net (code "87") (name "unconnected-(U5A-PD12-PadJ10)") (class "Default")
      (node (ref "U5") (pin "J10") (pinfunction "PD12_J10") (pintype "bidirectional"))
    )
    (net (code "88") (name "unconnected-(U5A-PD13-PadJ9)") (class "Default")
      (node (ref "U5") (pin "J9") (pinfunction "PD13_J9") (pintype "bidirectional"))
    )
    (net (code "89") (name "unconnected-(U5A-PD14-PadH9)") (class "Default")
      (node (ref "U5") (pin "H9") (pinfunction "PD14_H9") (pintype "bidirectional"))
    )
    (net (code "90") (name "unconnected-(U5A-PD15-PadH10)") (class "Default")
      (node (ref "U5") (pin "H10") (pinfunction "PD15_H10") (pintype "bidirectional"))
    )
    (net (code "91") (name "unconnected-(U5B-PE0-PadD4)") (class "Default")
      (node (ref "U5") (pin "D4") (pinfunction "PE0_D4") (pintype "bidirectional"))
    )
    (net (code "92") (name "unconnected-(U5B-PE1-PadC4)") (class "Default")
      (node (ref "U5") (pin "C4") (pinfunction "PE1_C4") (pintype "bidirectional"))
    )
    (net (code "93") (name "unconnected-(U5B-PE2-PadA2)") (class "Default")
      (node (ref "U5") (pin "A2") (pinfunction "PE2_A2") (pintype "bidirectional"))
    )
    (net (code "94") (name "unconnected-(U5B-PE3-PadC3)") (class "Default")
      (node (ref "U5") (pin "C3") (pinfunction "PE3_C3") (pintype "bidirectional"))
    )
    (net (code "95") (name "unconnected-(U5B-PE4-PadD3)") (class "Default")
      (node (ref "U5") (pin "D3") (pinfunction "PE4_D3") (pintype "bidirectional"))
    )
    (net (code "96") (name "unconnected-(U5B-PE5-PadE4)") (class "Default")
      (node (ref "U5") (pin "E4") (pinfunction "PE5_E4") (pintype "bidirectional"))
    )
    (net (code "97") (name "unconnected-(U5B-PE6-PadC2)") (class "Default")
      (node (ref "U5") (pin "C2") (pinfunction "PE6_C2") (pintype "bidirectional"))
    )
    (net (code "98") (name "unconnected-(U5B-PE7-PadK7)") (class "Default")
      (node (ref "U5") (pin "K7") (pinfunction "PE7_K7") (pintype "bidirectional"))
    )
    (net (code "99") (name "unconnected-(U5B-PE8-PadL8)") (class "Default")
      (node (ref "U5") (pin "L8") (pinfunction "PE8_L8") (pintype "bidirectional"))
    )
    (net (code "100") (name "unconnected-(U5B-PE9-PadN6)") (class "Default")
      (node (ref "U5") (pin "N6") (pinfunction "PE9_N6") (pintype "bidirectional"))
    )
    (net (code "101") (name "unconnected-(U5B-PE10-PadL7)") (class "Default")
      (node (ref "U5") (pin "L7") (pinfunction "PE10_L7") (pintype "bidirectional"))
    )
    (net (code "102") (name "unconnected-(U5B-PE11-PadN7)") (class "Default")
      (node (ref "U5") (pin "N7") (pinfunction "PE11_N7") (pintype "bidirectional"))
    )
    (net (code "103") (name "unconnected-(U5B-PE12-PadJ8)") (class "Default")
      (node (ref "U5") (pin "J8") (pinfunction "PE12_J8") (pintype "bidirectional"))
    )
    (net (code "104") (name "unconnected-(U5B-PE13-PadH8)") (class "Default")
      (node (ref "U5") (pin "H8") (pinfunction "PE13_H8") (pintype "bidirectional"))
    )
    (net (code "105") (name "unconnected-(U5B-PE14-PadM8)") (class "Default")
      (node (ref "U5") (pin "M8") (pinfunction "PE14_M8") (pintype "bidirectional"))
    )
    (net (code "106") (name "unconnected-(U5B-PE15-PadK8)") (class "Default")
      (node (ref "U5") (pin "K8") (pinfunction "PE15_K8") (pintype "bidirectional"))
    )
    (net (code "107") (name "unconnected-(U5B-PF2-PadF6)") (class "Default")
      (node (ref "U5") (pin "F6") (pinfunction "PF2_F6") (pintype "bidirectional"))
    )
    (net (code "108") (name "unconnected-(U5B-PF3-PadG2)") (class "Default")
      (node (ref "U5") (pin "G2") (pinfunction "PF3_G2") (pintype "bidirectional"))
    )
    (net (code "109") (name "unconnected-(U5B-PF4-PadG1)") (class "Default")
      (node (ref "U5") (pin "G1") (pinfunction "PF4_G1") (pintype "bidirectional"))
    )
    (net (code "110") (name "unconnected-(U5B-PF5-PadG3)") (class "Default")
      (node (ref "U5") (pin "G3") (pinfunction "PF5_G3") (pintype "bidirectional"))
    )
    (net (code "111") (name "unconnected-(U5B-PF6-PadG4)") (class "Default")
      (node (ref "U5") (pin "G4") (pinfunction "PF6_G4") (pintype "bidirectional"))
    )
    (net (code "112") (name "unconnected-(U5B-PF7-PadG5)") (class "Default")
      (node (ref "U5") (pin "G5") (pinfunction "PF7_G5") (pintype "bidirectional"))
    )
    (net (code "113") (name "unconnected-(U5B-PF8-PadG6)") (class "Default")
      (node (ref "U5") (pin "G6") (pinfunction "PF8_G6") (pintype "bidirectional"))
    )
    (net (code "114") (name "unconnected-(U5B-PF9-PadH3)") (class "Default")
      (node (ref "U5") (pin "H3") (pinfunction "PF9_H3") (pintype "bidirectional"))
    )
    (net (code "115") (name "unconnected-(U5B-PF10-PadH4)") (class "Default")
      (node (ref "U5") (pin "H4") (pinfunction "PF10_H4") (pintype "bidirectional"))
    )
    (net (code "116") (name "unconnected-(U5B-PF11-PadK6)") (class "Default")
      (node (ref "U5") (pin "K6") (pinfunction "PF11_K6") (pintype "bidirectional"))
    )
    (net (code "117") (name "unconnected-(U5B-PF12-PadJ6)") (class "Default")
      (node (ref "U5") (pin "J6") (pinfunction "PF12_J6") (pintype "bidirectional"))
    )
    (net (code "118") (name "unconnected-(U5B-PF13-PadM5)") (class "Default")
      (node (ref "U5") (pin "M5") (pinfunction "PF13_M5") (pintype "bidirectional"))
    )
    (net (code "119") (name "unconnected-(U5B-PG0-PadL6)") (class "Default")
      (node (ref "U5") (pin "L6") (pinfunction "PG0_L6") (pintype "bidirectional"))
    )
    (net (code "120") (name "unconnected-(U5B-PG1-PadJ7)") (class "Default")
      (node (ref "U5") (pin "J7") (pinfunction "PG1_J7") (pintype "bidirectional"))
    )
    (net (code "121") (name "unconnected-(U5B-PG2-PadH7)") (class "Default")
      (node (ref "U5") (pin "H7") (pinfunction "PG2_H7") (pintype "bidirectional"))
    )
    (net (code "122") (name "unconnected-(U5B-PG3-PadG8)") (class "Default")
      (node (ref "U5") (pin "G8") (pinfunction "PG3_G8") (pintype "bidirectional"))
    )
    (net (code "123") (name "unconnected-(U5B-PG4-PadG10)") (class "Default")
      (node (ref "U5") (pin "G10") (pinfunction "PG4_G10") (pintype "bidirectional"))
    )
    (net (code "124") (name "unconnected-(U5B-PG5-PadG9)") (class "Default")
      (node (ref "U5") (pin "G9") (pinfunction "PG5_G9") (pintype "bidirectional"))
    )
    (net (code "125") (name "unconnected-(U5B-PG6-PadG11)") (class "Default")
      (node (ref "U5") (pin "G11") (pinfunction "PG6_G11") (pintype "bidirectional"))
    )
    (net (code "126") (name "unconnected-(U5B-PG7-PadF8)") (class "Default")
      (node (ref "U5") (pin "F8") (pinfunction "PG7_F8") (pintype "bidirectional"))
    )
    (net (code "127") (name "unconnected-(U5B-PG8-PadF9)") (class "Default")
      (node (ref "U5") (pin "F9") (pinfunction "PG8_F9") (pintype "bidirectional"))
    )
    (net (code "128") (name "unconnected-(U5B-PG9-PadC7)") (class "Default")
      (node (ref "U5") (pin "C7") (pinfunction "PG9_C7") (pintype "bidirectional"))
    )
    (net (code "129") (name "unconnected-(U5B-PG10-PadD7)") (class "Default")
      (node (ref "U5") (pin "D7") (pinfunction "PG10_D7") (pintype "bidirectional"))
    )
    (net (code "130") (name "unconnected-(U5B-PG11-PadE7)") (class "Default")
      (node (ref "U5") (pin "E7") (pinfunction "PG11_E7") (pintype "bidirectional"))
    )
    (net (code "131") (name "unconnected-(U5B-PG12-PadG7)") (class "Default")
      (node (ref "U5") (pin "G7") (pinfunction "PG12_G7") (pintype "bidirectional"))
    )
    (net (code "132") (name "unconnected-(U5B-PG13-PadF7)") (class "Default")
      (node (ref "U5") (pin "F7") (pinfunction "PG13_F7") (pintype "bidirectional"))
    )
    (net (code "133") (name "unconnected-(U5B-PG14-PadE6)") (class "Default")
      (node (ref "U5") (pin "E6") (pinfunction "PG14_E6") (pintype "bidirectional"))
    )
    (net (code "134") (name "unconnected-(U5B-PG15-PadC6)") (class "Default")
      (node (ref "U5") (pin "C6") (pinfunction "PG15_C6") (pintype "bidirectional"))
    )
    (net (code "135") (name "unconnected-(U5C-VLXSMPS-PadE1)") (class "Default")
      (node (ref "U5") (pin "E1") (pinfunction "VLXSMPS_E1") (pintype "power_in+no_connect"))
    )
  )
)
